# ISL6236A.net
KiCad netlist of a schematic drawn in Altium Designer
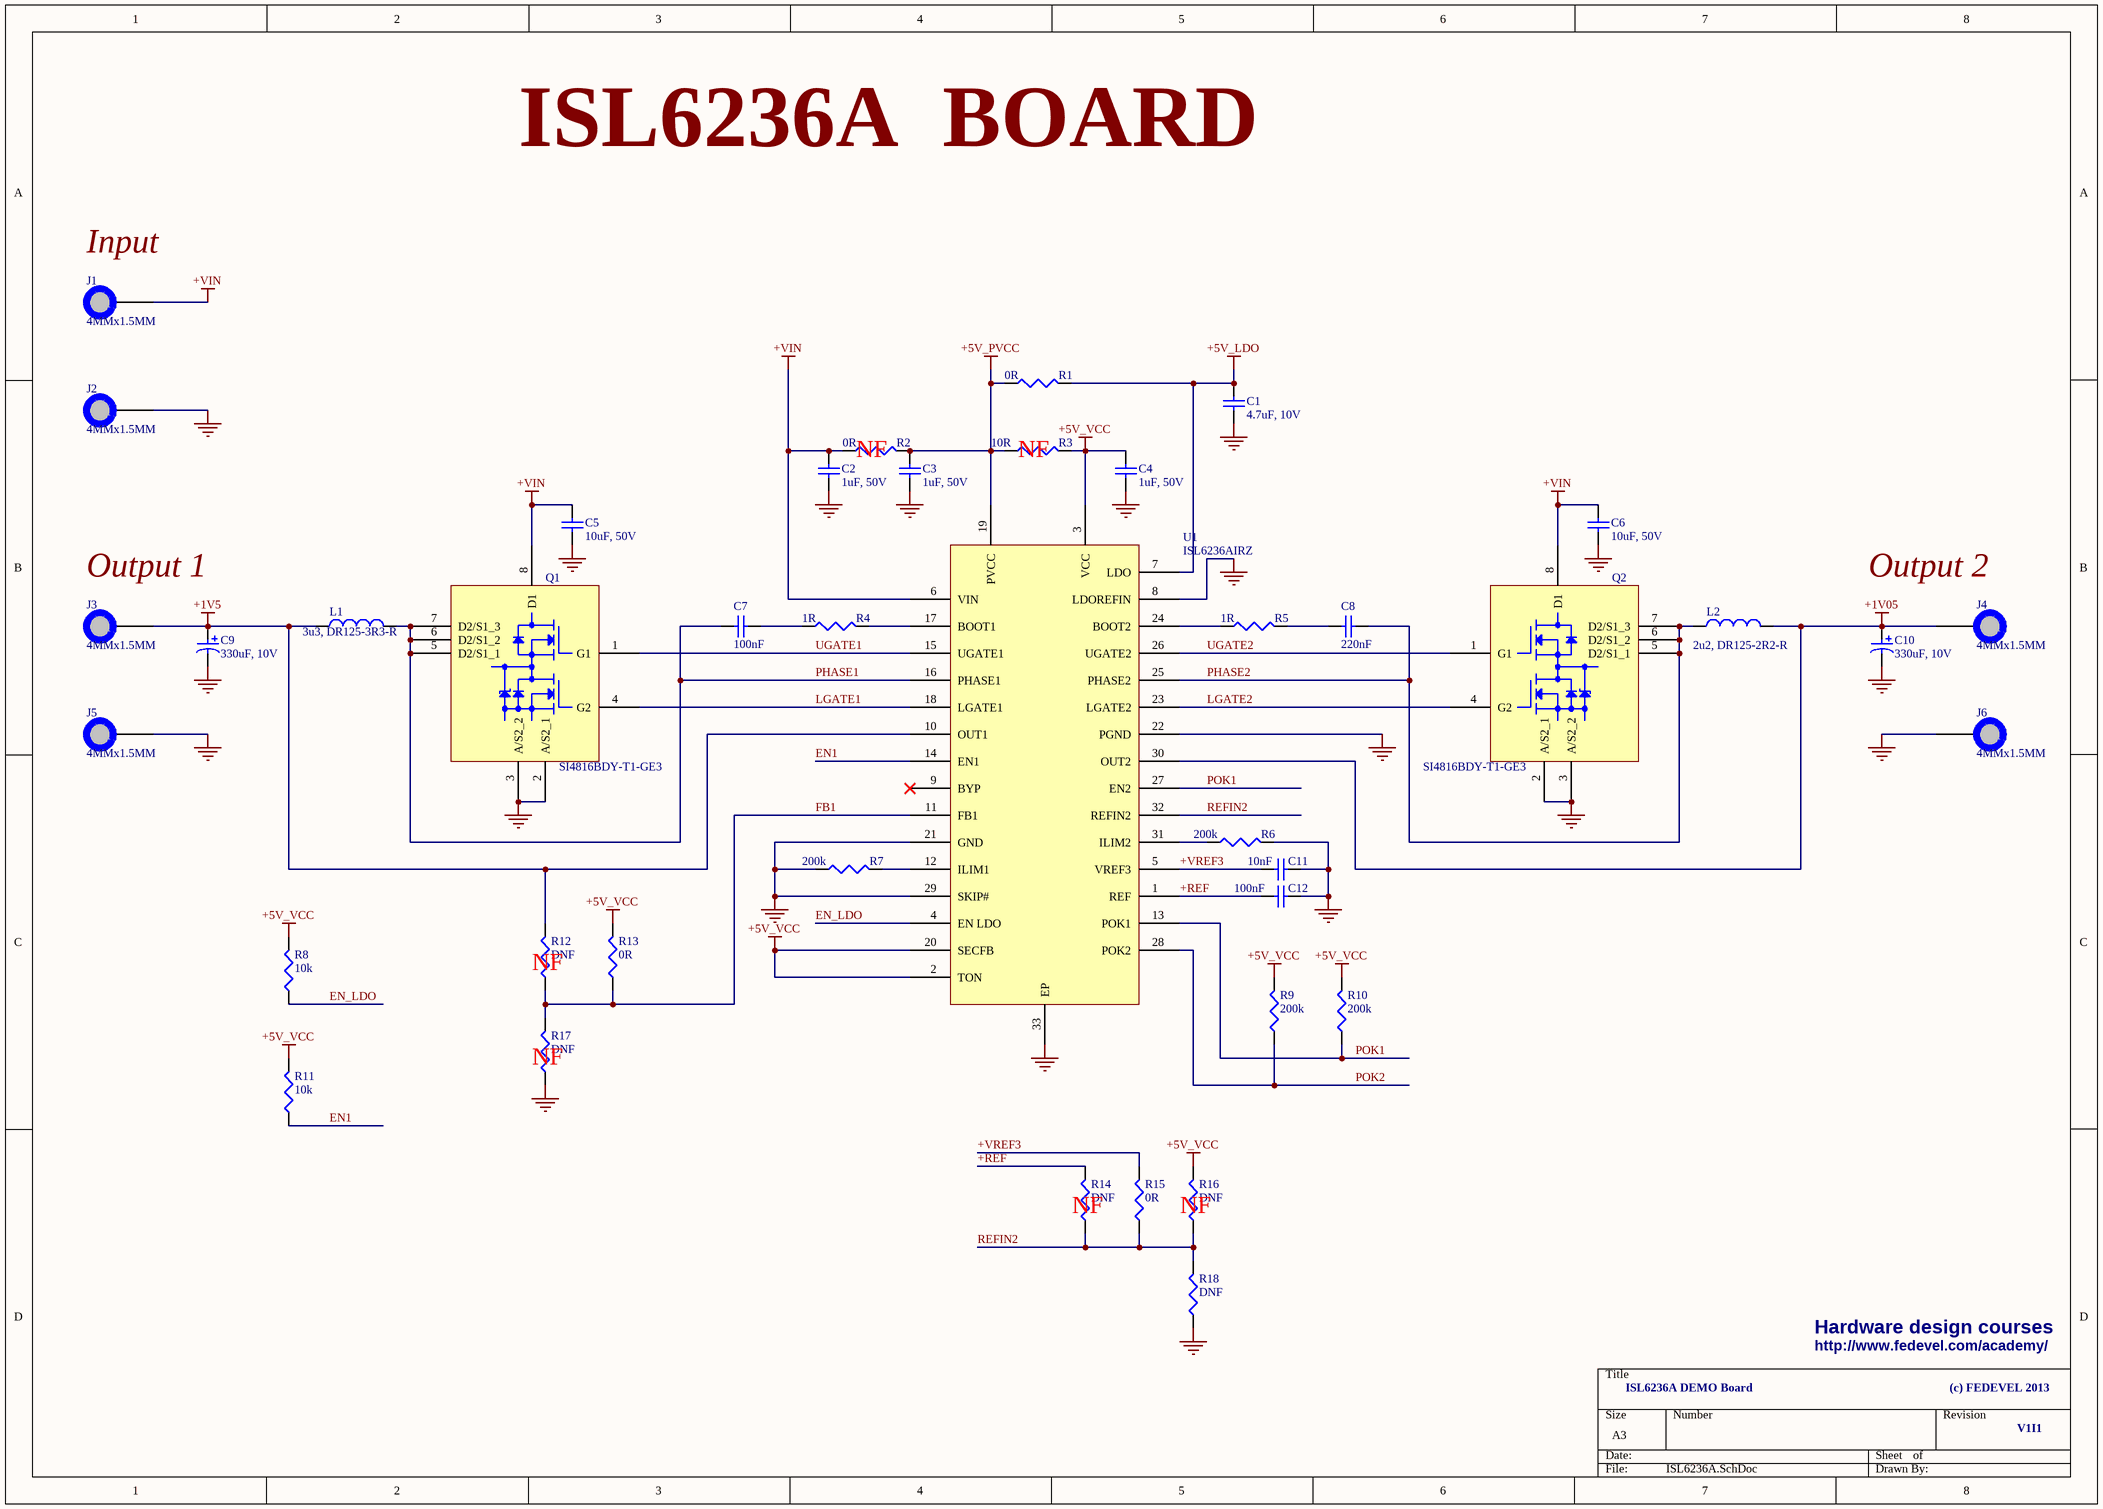
[diagram p0: ISL6236A.SchDoc]

(export (version "E")
  (design (tool "Eeschema 10.0.6"))
  (components
    (comp (ref "C1")
      (value "4.7uF, 10V")
      (footprint "C1206")
      (description "CAP CER 4.7UF 10V 10% X5R 1206")
      (fields
        (field (name "MANUFACTURER") "TDK Corporation")
        (field (name "MANUFACTURER PART NUMBER") "C3216X5R1A475K")
      )
      (libsource (lib "ISL6236A_DEMO") (part "C3216X5R1A475K"))
    )
    (comp (ref "C2")
      (value "1uF, 50V")
      (footprint "C0805")
      (description "CAP CER 1UF 50V 10% X7R 0805")
      (fields
        (field (name "MANUFACTURER") "TDK Corporation")
        (field (name "MANUFACTURER PART NUMBER") "C2012X7R1H105K125AB")
      )
      (libsource (lib "ISL6236A_DEMO") (part "C2012X7R1H105K125AB"))
    )
    (comp (ref "C3")
      (value "1uF, 50V")
      (footprint "C0805")
      (description "CAP CER 1UF 50V 10% X7R 0805")
      (fields
        (field (name "MANUFACTURER") "TDK Corporation")
        (field (name "MANUFACTURER PART NUMBER") "C2012X7R1H105K125AB")
      )
      (libsource (lib "ISL6236A_DEMO") (part "C2012X7R1H105K125AB"))
    )
    (comp (ref "C4")
      (value "1uF, 50V")
      (footprint "C0805")
      (description "CAP CER 1UF 50V 10% X7R 0805")
      (fields
        (field (name "MANUFACTURER") "TDK Corporation")
        (field (name "MANUFACTURER PART NUMBER") "C2012X7R1H105K125AB")
      )
      (libsource (lib "ISL6236A_DEMO") (part "C2012X7R1H105K125AB"))
    )
    (comp (ref "C5")
      (value "10uF, 50V")
      (footprint "C1210")
      (description "CAP CER 10UF 50V 20% X5R 1210")
      (fields
        (field (name "MANUFACTURER") "Taiyo Yuden")
        (field (name "MANUFACTURER PART NUMBER") "UMK325BJ106MM-T")
      )
      (libsource (lib "ISL6236A_DEMO") (part "UMK325BJ106MM-T"))
    )
    (comp (ref "C6")
      (value "10uF, 50V")
      (footprint "C1210")
      (description "CAP CER 10UF 50V 20% X5R 1210")
      (fields
        (field (name "MANUFACTURER") "Taiyo Yuden")
        (field (name "MANUFACTURER PART NUMBER") "UMK325BJ106MM-T")
      )
      (libsource (lib "ISL6236A_DEMO") (part "UMK325BJ106MM-T"))
    )
    (comp (ref "C7")
      (value "100nF")
      (footprint "C0805")
      (description "CAP CER 0.1UF 50V 10% X7R 0805")
      (fields
        (field (name "MANUFACTURER") "TDK Corporation")
        (field (name "MANUFACTURER PART NUMBER") "C2012X7R1H104K085AA")
      )
      (libsource (lib "ISL6236A_DEMO") (part "C2012X7R1H104K085AA"))
    )
    (comp (ref "C8")
      (value "220nF")
      (footprint "C0805")
      (description "CAP CER 0.22UF 50V 10% X7R 0805")
      (fields
        (field (name "MANUFACTURER") "TDK Corporation")
        (field (name "MANUFACTURER PART NUMBER") "C2012X7R1H224K125AA")
      )
      (libsource (lib "ISL6236A_DEMO") (part "C2012X7R1H224K125AA"))
    )
    (comp (ref "C9")
      (value "330uF, 10V")
      (footprint "7343-43")
      (description "CAP TANT 330UF 10V 20% 2917")
      (fields
        (field (name "MANUFACTURER") "Kemet")
        (field (name "MANUFACTURER PART NUMBER") "T530X337M010ATE004")
      )
      (libsource (lib "ISL6236A_DEMO") (part "T530X337M010ATE004"))
    )
    (comp (ref "C10")
      (value "330uF, 10V")
      (footprint "7343-43")
      (description "CAP TANT 330UF 10V 20% 2917")
      (fields
        (field (name "MANUFACTURER") "Kemet")
        (field (name "MANUFACTURER PART NUMBER") "T530X337M010ATE004")
      )
      (libsource (lib "ISL6236A_DEMO") (part "T530X337M010ATE004"))
    )
    (comp (ref "C11")
      (value "10nF")
      (footprint "C0805")
      (description "CAP CER 10000PF 50V 10% X7R 0805")
      (fields
        (field (name "MANUFACTURER") "Vishay Vitramon")
        (field (name "MANUFACTURER PART NUMBER") "VJ0805Y103KNAAO")
      )
      (libsource (lib "ISL6236A_DEMO") (part "VJ0805Y103KNAAO"))
    )
    (comp (ref "C12")
      (value "100nF")
      (footprint "C0805")
      (description "CAP CER 0.1UF 50V 10% X7R 0805")
      (fields
        (field (name "MANUFACTURER") "TDK Corporation")
        (field (name "MANUFACTURER PART NUMBER") "C2012X7R1H104K085AA")
      )
      (libsource (lib "ISL6236A_DEMO") (part "C2012X7R1H104K085AA"))
    )
    (comp (ref "J1")
      (value "4MMx1.5MM")
      (footprint "PAD_WITH_HOLE_4MMx1.5MM")
      (description "Pad with a hole 4mm x 1.5mm")
      (libsource (lib "ISL6236A_DEMO") (part "PAD_WITH_HOLE_4MMx1.5MM"))
    )
    (comp (ref "J2")
      (value "4MMx1.5MM")
      (footprint "PAD_WITH_HOLE_4MMx1.5MM")
      (description "Pad with a hole 4mm x 1.5mm")
      (libsource (lib "ISL6236A_DEMO") (part "PAD_WITH_HOLE_4MMx1.5MM"))
    )
    (comp (ref "J3")
      (value "4MMx1.5MM")
      (footprint "PAD_WITH_HOLE_4MMx1.5MM")
      (description "Pad with a hole 4mm x 1.5mm")
      (libsource (lib "ISL6236A_DEMO") (part "PAD_WITH_HOLE_4MMx1.5MM"))
    )
    (comp (ref "J4")
      (value "4MMx1.5MM")
      (footprint "PAD_WITH_HOLE_4MMx1.5MM")
      (description "Pad with a hole 4mm x 1.5mm")
      (libsource (lib "ISL6236A_DEMO") (part "PAD_WITH_HOLE_4MMx1.5MM"))
    )
    (comp (ref "J5")
      (value "4MMx1.5MM")
      (footprint "PAD_WITH_HOLE_4MMx1.5MM")
      (description "Pad with a hole 4mm x 1.5mm")
      (libsource (lib "ISL6236A_DEMO") (part "PAD_WITH_HOLE_4MMx1.5MM"))
    )
    (comp (ref "J6")
      (value "4MMx1.5MM")
      (footprint "PAD_WITH_HOLE_4MMx1.5MM")
      (description "Pad with a hole 4mm x 1.5mm")
      (libsource (lib "ISL6236A_DEMO") (part "PAD_WITH_HOLE_4MMx1.5MM"))
    )
    (comp (ref "L1")
      (value "3u3, DR125-3R3-R")
      (footprint "DR125")
      (description "INDUCTOR SHIELD PWR 3.3UH SMD")
      (fields
        (field (name "MANUFACTURER") "Cooper Bussmann")
        (field (name "MANUFACTURER PART NUMBER") "DR125-3R3-R")
      )
      (libsource (lib "ISL6236A_DEMO") (part "DR125-3R3-R"))
    )
    (comp (ref "L2")
      (value "2u2, DR125-2R2-R")
      (footprint "DR125")
      (description "INDUCTOR SHIELD PWR 2.2UH SMD")
      (fields
        (field (name "MANUFACTURER") "Cooper Bussmann")
        (field (name "MANUFACTURER PART NUMBER") "DR125-2R2-R")
      )
      (libsource (lib "ISL6236A_DEMO") (part "DR125-2R2-R"))
    )
    (comp (ref "Q1")
      (value "SI4816BDY-T1-GE3")
      (footprint "SO-8")
      (description "MOSFET DL N-CH 30V 6.8A 8-SOIC")
      (fields (field (name "MANUFACTURER") "Vishay Siliconix"))
      (libsource (lib "ISL6236A_DEMO") (part "SI4816BDY-T1-GE3"))
    )
    (comp (ref "Q2")
      (value "SI4816BDY-T1-GE3")
      (footprint "SO-8")
      (description "MOSFET DL N-CH 30V 6.8A 8-SOIC")
      (fields (field (name "MANUFACTURER") "Vishay Siliconix"))
      (libsource (lib "") (part "SI4816BDY-T1-GE3_1"))
    )
    (comp (ref "R1")
      (value "0R")
      (footprint "R0805")
      (description "RES 0.0 OHM 1/8W JUMP 0805 SMD")
      (fields
        (field (name "MANUFACTURER") "Panasonic Electronic Components")
        (field (name "MANUFACTURER PART NUMBER") "ERJ-6GEY0R00V")
      )
      (libsource (lib "ISL6236A_DEMO") (part "ERJ-6GEY0R00V"))
    )
    (comp (ref "R2")
      (value "0R")
      (footprint "R0805")
      (description "RES 0.0 OHM 1/8W JUMP 0805 SMD")
      (fields
        (field (name "MANUFACTURER") "Panasonic Electronic Components")
        (field (name "MANUFACTURER PART NUMBER") "ERJ-6GEY0R00V")
      )
      (libsource (lib "ISL6236A_DEMO") (part "ERJ-6GEY0R00V"))
    )
    (comp (ref "R3")
      (value "10R")
      (footprint "R0805")
      (description "RES 10 OHM 1/8W 5% 0805 SMD")
      (fields
        (field (name "MANUFACTURER") "Panasonic Electronic Components")
        (field (name "MANUFACTURER PART NUMBER") "ERJ-6GEYJ100V")
      )
      (libsource (lib "ISL6236A_DEMO") (part "ERJ-6GEYJ100V"))
    )
    (comp (ref "R4")
      (value "1R")
      (footprint "R0805")
      (description "RES 1 OHM 1/8W 1% 0805 SMD")
      (fields
        (field (name "MANUFACTURER") "Panasonic Electronic Components")
        (field (name "MANUFACTURER PART NUMBER") "ERJ-6RQF1R0V")
      )
      (libsource (lib "ISL6236A_DEMO") (part "ERJ-6RQF1R0V"))
    )
    (comp (ref "R5")
      (value "1R")
      (footprint "R0805")
      (description "RES 1 OHM 1/8W 1% 0805 SMD")
      (fields
        (field (name "MANUFACTURER") "Panasonic Electronic Components")
        (field (name "MANUFACTURER PART NUMBER") "ERJ-6RQF1R0V")
      )
      (libsource (lib "ISL6236A_DEMO") (part "ERJ-6RQF1R0V"))
    )
    (comp (ref "R6")
      (value "200k")
      (footprint "R0805")
      (description "RES 200K OHM 1/8W 1% 0805 SMD")
      (fields
        (field (name "MANUFACTURER") "Panasonic Electronic Components")
        (field (name "MANUFACTURER PART NUMBER") "ERJ-6ENF2003V")
      )
      (libsource (lib "ISL6236A_DEMO") (part "ERJ-6ENF2003V"))
    )
    (comp (ref "R7")
      (value "200k")
      (footprint "R0805")
      (description "RES 200K OHM 1/8W 1% 0805 SMD")
      (fields
        (field (name "MANUFACTURER") "Panasonic Electronic Components")
        (field (name "MANUFACTURER PART NUMBER") "ERJ-6ENF2003V")
      )
      (libsource (lib "ISL6236A_DEMO") (part "ERJ-6ENF2003V"))
    )
    (comp (ref "R8")
      (value "10k")
      (footprint "R0805")
      (description "RES 10K OHM 1/8W 5% 0805 SMD")
      (fields
        (field (name "MANUFACTURER") "Panasonic Electronic Components")
        (field (name "MANUFACTURER PART NUMBER") "ERJ-6GEYJ103V")
      )
      (libsource (lib "ISL6236A_DEMO") (part "ERJ-6GEYJ103V"))
    )
    (comp (ref "R9")
      (value "200k")
      (footprint "R0805")
      (description "RES 200K OHM 1/8W 1% 0805 SMD")
      (fields
        (field (name "MANUFACTURER") "Panasonic Electronic Components")
        (field (name "MANUFACTURER PART NUMBER") "ERJ-6ENF2003V")
      )
      (libsource (lib "ISL6236A_DEMO") (part "ERJ-6ENF2003V"))
    )
    (comp (ref "R10")
      (value "200k")
      (footprint "R0805")
      (description "RES 200K OHM 1/8W 1% 0805 SMD")
      (fields
        (field (name "MANUFACTURER") "Panasonic Electronic Components")
        (field (name "MANUFACTURER PART NUMBER") "ERJ-6ENF2003V")
      )
      (libsource (lib "ISL6236A_DEMO") (part "ERJ-6ENF2003V"))
    )
    (comp (ref "R11")
      (value "10k")
      (footprint "R0805")
      (description "RES 10K OHM 1/8W 5% 0805 SMD")
      (fields
        (field (name "MANUFACTURER") "Panasonic Electronic Components")
        (field (name "MANUFACTURER PART NUMBER") "ERJ-6GEYJ103V")
      )
      (libsource (lib "ISL6236A_DEMO") (part "ERJ-6GEYJ103V"))
    )
    (comp (ref "R12") (value "DNF") (footprint "R0805") (libsource (lib "ISL6236A_DEMO") (part "RES")))
    (comp (ref "R13")
      (value "0R")
      (footprint "R0805")
      (description "RES 0.0 OHM 1/8W JUMP 0805 SMD")
      (fields
        (field (name "MANUFACTURER") "Panasonic Electronic Components")
        (field (name "MANUFACTURER PART NUMBER") "ERJ-6GEY0R00V")
      )
      (libsource (lib "ISL6236A_DEMO") (part "ERJ-6GEY0R00V"))
    )
    (comp (ref "R14") (value "DNF") (footprint "R0805") (libsource (lib "ISL6236A_DEMO") (part "RES")))
    (comp (ref "R15")
      (value "0R")
      (footprint "R0805")
      (description "RES 0.0 OHM 1/8W JUMP 0805 SMD")
      (fields
        (field (name "MANUFACTURER") "Panasonic Electronic Components")
        (field (name "MANUFACTURER PART NUMBER") "ERJ-6GEY0R00V")
      )
      (libsource (lib "ISL6236A_DEMO") (part "ERJ-6GEY0R00V"))
    )
    (comp (ref "R16") (value "DNF") (footprint "R0805") (libsource (lib "ISL6236A_DEMO") (part "RES")))
    (comp (ref "R17") (value "DNF") (footprint "R0805") (libsource (lib "ISL6236A_DEMO") (part "RES")))
    (comp (ref "R18") (value "DNF") (footprint "R0805") (libsource (lib "ISL6236A_DEMO") (part "RES")))
    (comp (ref "U1")
      (value "ISL6236AIRZ")
      (footprint "L32.5x5B")
      (description "IC MAIN PWR CTRLR QUAD 32-QFN")
      (fields (field (name "MANUFACTURER") "Intersil"))
      (libsource (lib "ISL6236A_DEMO") (part "ISL6236AIRZ"))
    )
  )
  (nets
    (net (code "1") (name "+1V5") (class "Default")
      (node (ref "C9") (pin "1") (pinfunction "1_1") (pintype "passive"))
      (node (ref "J3") (pin "1") (pinfunction "1_1") (pintype "passive"))
      (node (ref "L1") (pin "1") (pinfunction "1_1") (pintype "passive"))
      (node (ref "R12") (pin "2") (pinfunction "2_2") (pintype "passive"))
      (node (ref "U1") (pin "10") (pinfunction "OUT1_10") (pintype "passive"))
    )
    (net (code "2") (name "+1V05") (class "Default")
      (node (ref "C10") (pin "1") (pinfunction "1_1") (pintype "passive"))
      (node (ref "J4") (pin "1") (pinfunction "1_1") (pintype "passive"))
      (node (ref "L2") (pin "2") (pinfunction "2_2") (pintype "passive"))
      (node (ref "U1") (pin "30") (pinfunction "OUT2_30") (pintype "passive"))
    )
    (net (code "3") (name "+5V_LDO") (class "Default")
      (node (ref "C1") (pin "2") (pinfunction "2_2") (pintype "passive"))
      (node (ref "R1") (pin "2") (pinfunction "2_2") (pintype "passive"))
      (node (ref "U1") (pin "7") (pinfunction "LDO_7") (pintype "passive"))
    )
    (net (code "4") (name "+5V_PVCC") (class "Default")
      (node (ref "C3") (pin "2") (pinfunction "2_2") (pintype "passive"))
      (node (ref "R1") (pin "1") (pinfunction "1_1") (pintype "passive"))
      (node (ref "R2") (pin "2") (pinfunction "2_2") (pintype "passive"))
      (node (ref "R3") (pin "1") (pinfunction "1_1") (pintype "passive"))
      (node (ref "U1") (pin "19") (pinfunction "PVCC_19") (pintype "passive"))
    )
    (net (code "5") (name "+5V_VCC") (class "Default")
      (node (ref "C4") (pin "2") (pinfunction "2_2") (pintype "passive"))
      (node (ref "R10") (pin "2") (pinfunction "2_2") (pintype "passive"))
      (node (ref "R11") (pin "2") (pinfunction "2_2") (pintype "passive"))
      (node (ref "R13") (pin "2") (pinfunction "2_2") (pintype "passive"))
      (node (ref "R16") (pin "2") (pinfunction "2_2") (pintype "passive"))
      (node (ref "R3") (pin "2") (pinfunction "2_2") (pintype "passive"))
      (node (ref "R8") (pin "2") (pinfunction "2_2") (pintype "passive"))
      (node (ref "R9") (pin "2") (pinfunction "2_2") (pintype "passive"))
      (node (ref "U1") (pin "2") (pinfunction "TON_2") (pintype "passive"))
      (node (ref "U1") (pin "20") (pinfunction "SECFB_20") (pintype "passive"))
      (node (ref "U1") (pin "3") (pinfunction "VCC_3") (pintype "passive"))
    )
    (net (code "6") (name "+VIN") (class "Default")
      (node (ref "C2") (pin "2") (pinfunction "2_2") (pintype "passive"))
      (node (ref "C5") (pin "2") (pinfunction "2_2") (pintype "passive"))
      (node (ref "C6") (pin "2") (pinfunction "2_2") (pintype "passive"))
      (node (ref "J1") (pin "1") (pinfunction "1_1") (pintype "passive"))
      (node (ref "Q1") (pin "8") (pinfunction "D1_8") (pintype "passive"))
      (node (ref "Q2") (pin "8") (pinfunction "D1_8") (pintype "passive"))
      (node (ref "R2") (pin "1") (pinfunction "1_1") (pintype "passive"))
      (node (ref "U1") (pin "6") (pinfunction "VIN_6") (pintype "passive"))
    )
    (net (code "7") (name "/+REF") (class "Default")
      (node (ref "C12") (pin "1") (pinfunction "1_1") (pintype "passive"))
      (node (ref "R14") (pin "2") (pinfunction "2_2") (pintype "passive"))
      (node (ref "U1") (pin "1") (pinfunction "REF_1") (pintype "passive"))
    )
    (net (code "8") (name "/+VREF3") (class "Default")
      (node (ref "C11") (pin "1") (pinfunction "1_1") (pintype "passive"))
      (node (ref "R15") (pin "2") (pinfunction "2_2") (pintype "passive"))
      (node (ref "U1") (pin "5") (pinfunction "VREF3_5") (pintype "passive"))
    )
    (net (code "9") (name "/EN1") (class "Default")
      (node (ref "R11") (pin "1") (pinfunction "1_1") (pintype "passive"))
      (node (ref "U1") (pin "14") (pinfunction "EN1_14") (pintype "passive"))
    )
    (net (code "10") (name "/EN_LDO") (class "Default")
      (node (ref "R8") (pin "1") (pinfunction "1_1") (pintype "passive"))
      (node (ref "U1") (pin "4") (pinfunction "EN_LDO_4") (pintype "passive"))
    )
    (net (code "11") (name "/FB1") (class "Default")
      (node (ref "R12") (pin "1") (pinfunction "1_1") (pintype "passive"))
      (node (ref "R13") (pin "1") (pinfunction "1_1") (pintype "passive"))
      (node (ref "R17") (pin "2") (pinfunction "2_2") (pintype "passive"))
      (node (ref "U1") (pin "11") (pinfunction "FB1_11") (pintype "passive"))
    )
    (net (code "12") (name "/LGATE1") (class "Default")
      (node (ref "Q1") (pin "4") (pinfunction "G2_4") (pintype "passive"))
      (node (ref "U1") (pin "18") (pinfunction "LGATE1_18") (pintype "passive"))
    )
    (net (code "13") (name "/LGATE2") (class "Default")
      (node (ref "Q2") (pin "4") (pinfunction "G2_4") (pintype "passive"))
      (node (ref "U1") (pin "23") (pinfunction "LGATE2_23") (pintype "passive"))
    )
    (net (code "14") (name "/PHASE1") (class "Default")
      (node (ref "C7") (pin "1") (pinfunction "1_1") (pintype "passive"))
      (node (ref "L1") (pin "2") (pinfunction "2_2") (pintype "passive"))
      (node (ref "Q1") (pin "5") (pinfunction "D2/S1_1_5") (pintype "passive"))
      (node (ref "Q1") (pin "6") (pinfunction "D2/S1_2_6") (pintype "passive"))
      (node (ref "Q1") (pin "7") (pinfunction "D2/S1_3_7") (pintype "passive"))
      (node (ref "U1") (pin "16") (pinfunction "PHASE1_16") (pintype "passive"))
    )
    (net (code "15") (name "/PHASE2") (class "Default")
      (node (ref "C8") (pin "2") (pinfunction "2_2") (pintype "passive"))
      (node (ref "L2") (pin "1") (pinfunction "1_1") (pintype "passive"))
      (node (ref "Q2") (pin "5") (pinfunction "D2/S1_1_5") (pintype "passive"))
      (node (ref "Q2") (pin "6") (pinfunction "D2/S1_2_6") (pintype "passive"))
      (node (ref "Q2") (pin "7") (pinfunction "D2/S1_3_7") (pintype "passive"))
      (node (ref "U1") (pin "25") (pinfunction "PHASE2_25") (pintype "passive"))
    )
    (net (code "16") (name "/POK1") (class "Default")
      (node (ref "R10") (pin "1") (pinfunction "1_1") (pintype "passive"))
      (node (ref "U1") (pin "13") (pinfunction "POK1_13") (pintype "passive"))
      (node (ref "U1") (pin "27") (pinfunction "EN2_27") (pintype "passive"))
    )
    (net (code "17") (name "/POK2") (class "Default")
      (node (ref "R9") (pin "1") (pinfunction "1_1") (pintype "passive"))
      (node (ref "U1") (pin "28") (pinfunction "POK2_28") (pintype "passive"))
    )
    (net (code "18") (name "/REFIN2") (class "Default")
      (node (ref "R14") (pin "1") (pinfunction "1_1") (pintype "passive"))
      (node (ref "R15") (pin "1") (pinfunction "1_1") (pintype "passive"))
      (node (ref "R16") (pin "1") (pinfunction "1_1") (pintype "passive"))
      (node (ref "R18") (pin "2") (pinfunction "2_2") (pintype "passive"))
      (node (ref "U1") (pin "32") (pinfunction "REFIN2_32") (pintype "passive"))
    )
    (net (code "19") (name "/UGATE1") (class "Default")
      (node (ref "Q1") (pin "1") (pinfunction "G1_1") (pintype "passive"))
      (node (ref "U1") (pin "15") (pinfunction "UGATE1_15") (pintype "passive"))
    )
    (net (code "20") (name "/UGATE2") (class "Default")
      (node (ref "Q2") (pin "1") (pinfunction "G1_1") (pintype "passive"))
      (node (ref "U1") (pin "26") (pinfunction "UGATE2_26") (pintype "passive"))
    )
    (net (code "21") (name "GND") (class "Default")
      (node (ref "C1") (pin "1") (pinfunction "1_1") (pintype "passive"))
      (node (ref "C10") (pin "2") (pinfunction "2_2") (pintype "passive"))
      (node (ref "C11") (pin "2") (pinfunction "2_2") (pintype "passive"))
      (node (ref "C12") (pin "2") (pinfunction "2_2") (pintype "passive"))
      (node (ref "C2") (pin "1") (pinfunction "1_1") (pintype "passive"))
      (node (ref "C3") (pin "1") (pinfunction "1_1") (pintype "passive"))
      (node (ref "C4") (pin "1") (pinfunction "1_1") (pintype "passive"))
      (node (ref "C5") (pin "1") (pinfunction "1_1") (pintype "passive"))
      (node (ref "C6") (pin "1") (pinfunction "1_1") (pintype "passive"))
      (node (ref "C9") (pin "2") (pinfunction "2_2") (pintype "passive"))
      (node (ref "J2") (pin "1") (pinfunction "1_1") (pintype "passive"))
      (node (ref "J5") (pin "1") (pinfunction "1_1") (pintype "passive"))
      (node (ref "J6") (pin "1") (pinfunction "1_1") (pintype "passive"))
      (node (ref "Q1") (pin "2") (pinfunction "A/S2_1_2") (pintype "passive"))
      (node (ref "Q1") (pin "3") (pinfunction "A/S2_2_3") (pintype "passive"))
      (node (ref "Q2") (pin "2") (pinfunction "A/S2_1_2") (pintype "passive"))
      (node (ref "Q2") (pin "3") (pinfunction "A/S2_2_3") (pintype "passive"))
      (node (ref "R17") (pin "1") (pinfunction "1_1") (pintype "passive"))
      (node (ref "R18") (pin "1") (pinfunction "1_1") (pintype "passive"))
      (node (ref "R6") (pin "2") (pinfunction "2_2") (pintype "passive"))
      (node (ref "R7") (pin "1") (pinfunction "1_1") (pintype "passive"))
      (node (ref "U1") (pin "21") (pinfunction "GND_21") (pintype "passive"))
      (node (ref "U1") (pin "22") (pinfunction "PGND_22") (pintype "passive"))
      (node (ref "U1") (pin "29") (pinfunction "SKIP#_29") (pintype "passive"))
      (node (ref "U1") (pin "33") (pinfunction "EP_33") (pintype "passive"))
      (node (ref "U1") (pin "8") (pinfunction "LDOREFIN_8") (pintype "passive"))
    )
    (net (code "22") (name "Net-(C7-Pad2)") (class "Default")
      (node (ref "C7") (pin "2") (pinfunction "2_2") (pintype "passive"))
      (node (ref "R4") (pin "1") (pinfunction "1_1") (pintype "passive"))
    )
    (net (code "23") (name "Net-(C8-Pad1)") (class "Default")
      (node (ref "C8") (pin "1") (pinfunction "1_1") (pintype "passive"))
      (node (ref "R5") (pin "2") (pinfunction "2_2") (pintype "passive"))
    )
    (net (code "24") (name "Net-(U1-BOOT1)") (class "Default")
      (node (ref "R4") (pin "2") (pinfunction "2_2") (pintype "passive"))
      (node (ref "U1") (pin "17") (pinfunction "BOOT1_17") (pintype "passive"))
    )
    (net (code "25") (name "Net-(U1-BOOT2)") (class "Default")
      (node (ref "R5") (pin "1") (pinfunction "1_1") (pintype "passive"))
      (node (ref "U1") (pin "24") (pinfunction "BOOT2_24") (pintype "passive"))
    )
    (net (code "26") (name "Net-(U1-ILIM1)") (class "Default")
      (node (ref "R7") (pin "2") (pinfunction "2_2") (pintype "passive"))
      (node (ref "U1") (pin "12") (pinfunction "ILIM1_12") (pintype "passive"))
    )
    (net (code "27") (name "Net-(U1-ILIM2)") (class "Default")
      (node (ref "R6") (pin "1") (pinfunction "1_1") (pintype "passive"))
      (node (ref "U1") (pin "31") (pinfunction "ILIM2_31") (pintype "passive"))
    )
    (net (code "28") (name "unconnected-(U1-BYP-Pad9)") (class "Default")
      (node (ref "U1") (pin "9") (pinfunction "BYP_9") (pintype "passive+no_connect"))
    )
  )
)
